# Sheet1.net
KiCad netlist of a schematic drawn in Altium Designer
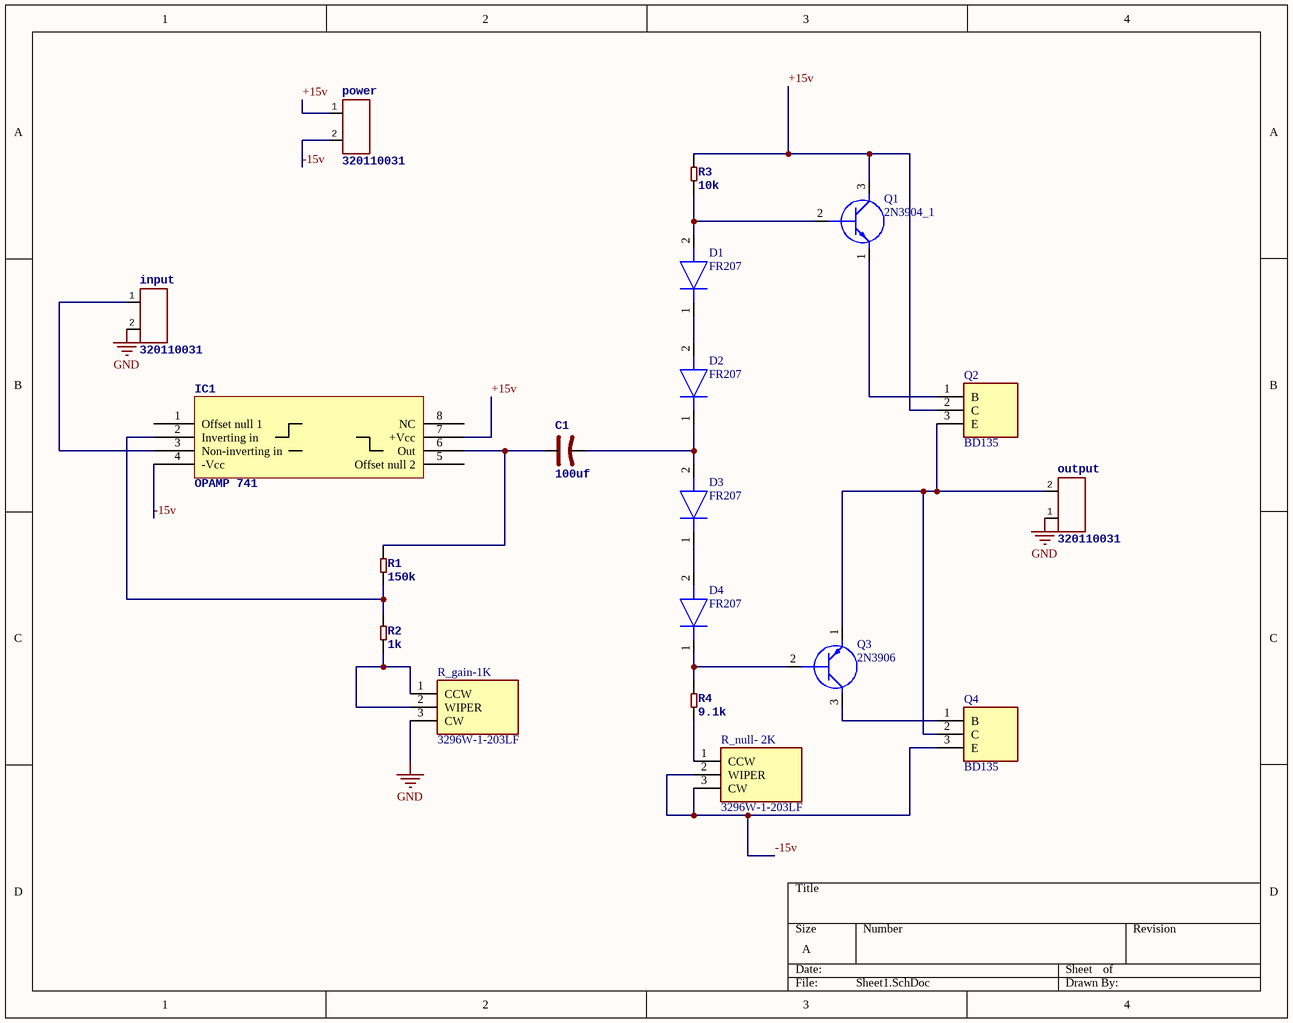
[diagram p0: Sheet1.SchDoc]

(export (version "E")
  (design (tool "Eeschema 10.0.6"))
  (components
    (comp (ref "C1")
      (value "100uf")
      (footprint "CAP TH")
      (libsource (lib "AltiumLibraryDDT") (part "CAP THT"))
    )
    (comp (ref "D1")
      (value "FR207")
      (footprint "SamacSys:DIOAD1910W90L670D310")
      (description "Diode")
      (libsource (lib "*") (part "FR207"))
    )
    (comp (ref "D2")
      (value "FR207")
      (footprint "SamacSys:DIOAD1910W90L670D310")
      (description "Diode")
      (libsource (lib "*") (part "FR207"))
    )
    (comp (ref "D3")
      (value "FR207")
      (footprint "SamacSys:DIOAD1910W90L670D310")
      (description "Diode")
      (libsource (lib "*") (part "FR207"))
    )
    (comp (ref "D4")
      (value "FR207")
      (footprint "SamacSys:DIOAD1910W90L670D310")
      (description "Diode")
      (libsource (lib "*") (part "FR207"))
    )
    (comp (ref "IC1")
      (value "OPAMP 741")
      (footprint "DIL08-ROUND")
      (libsource (lib "AltiumLibraryDDT") (part "OPAMP 741"))
    )
    (comp (ref "input")
      (value "320110031")
      (footprint "H2-5.0-10.5X8.0MM")
      (libsource (lib "AltiumLibraryDDT") (part "SCREW-TERMINAL-GREEN(2P-5.0)"))
    )
    (comp (ref "output")
      (value "320110031")
      (footprint "H2-5.0-10.5X8.0MM")
      (libsource (lib "AltiumLibraryDDT") (part "SCREW-TERMINAL-GREEN(2P-5.0)"))
    )
    (comp (ref "power")
      (value "320110031")
      (footprint "H2-5.0-10.5X8.0MM")
      (libsource (lib "AltiumLibraryDDT") (part "SCREW-TERMINAL-GREEN(2P-5.0)"))
    )
    (comp (ref "Q1")
      (value "2N3904_1")
      (footprint "SamacSys:LM431ACZ")
      (description "Transistor BJT NPN")
      (fields
        (field (name "MANUFACTURER_PART_NUMBER") "2N3904BU")
        (field (name "MOUSER PART NUMBER") "512-2N3904BU")
      )
      (libsource (lib "SamacSys") (part "2N3904_1"))
    )
    (comp (ref "Q2")
      (value "BD135")
      (footprint "SamacSys:TO254P290X760X1320-3P")
      (description "Integrated Circuit")
      (fields (field (name "MOUSER PART NUMBER") "511-BD135"))
      (libsource (lib "SamacSys") (part "BD135"))
    )
    (comp (ref "Q3")
      (value "2N3906")
      (footprint "SamacSys:2N5457")
      (description "Transistor BJT PNP")
      (fields (field (name "MOUSER PART NUMBER") "610-2N3906"))
      (libsource (lib "*") (part "2N3906"))
    )
    (comp (ref "Q4")
      (value "BD135")
      (footprint "SamacSys:TO254P290X760X1320-3P")
      (description "Integrated Circuit")
      (fields (field (name "MOUSER PART NUMBER") "511-BD135"))
      (libsource (lib "SamacSys") (part "BD135"))
    )
    (comp (ref "R1")
      (value "150k")
      (footprint "Res 1/4w")
      (libsource (lib "AltiumLibraryDDT") (part "RES_THT"))
    )
    (comp (ref "R2")
      (value "1k")
      (footprint "Res 1/4w")
      (libsource (lib "AltiumLibraryDDT") (part "RES_THT"))
    )
    (comp (ref "R3")
      (value "10k")
      (footprint "Res 1/4w")
      (libsource (lib "AltiumLibraryDDT") (part "RES_THT"))
    )
    (comp (ref "R4")
      (value "9.1k")
      (footprint "Res 1/4w")
      (libsource (lib "AltiumLibraryDDT") (part "RES_THT"))
    )
    (comp (ref "R_gain-1K")
      (value "3296W-1-203LF")
      (footprint "SamacSys:3296W-1")
      (description "Resistor")
      (fields (field (name "MOUSER PART NUMBER") "652-3296W-1-203LF"))
      (libsource (lib "*") (part "3296W-1-203LF"))
    )
    (comp (ref "R_null- 2K")
      (value "3296W-1-203LF")
      (footprint "SamacSys:3296W-1")
      (description "Resistor")
      (fields (field (name "MOUSER PART NUMBER") "652-3296W-1-203LF"))
      (libsource (lib "*") (part "3296W-1-203LF"))
    )
  )
  (nets
    (net (code "1") (name "/+15v") (class "Default")
      (node (ref "IC1") (pin "7") (pinfunction "+Vcc_7") (pintype "power_in"))
      (node (ref "Q1") (pin "3") (pinfunction "C_3") (pintype "passive"))
      (node (ref "Q2") (pin "2") (pinfunction "C_2") (pintype "passive"))
      (node (ref "R3") (pin "2") (pinfunction "2_2") (pintype "passive"))
      (node (ref "power") (pin "1") (pinfunction "1_1") (pintype "passive"))
    )
    (net (code "2") (name "/-15v") (class "Default")
      (node (ref "IC1") (pin "4") (pinfunction "-Vcc_4") (pintype "power_in"))
      (node (ref "Q4") (pin "3") (pinfunction "E_3") (pintype "passive"))
      (node (ref "R_null- 2K") (pin "2") (pinfunction "WIPER_2") (pintype "passive"))
      (node (ref "R_null- 2K") (pin "3") (pinfunction "CW_3") (pintype "passive"))
      (node (ref "power") (pin "2") (pinfunction "2_2") (pintype "passive"))
    )
    (net (code "3") (name "GND") (class "Default")
      (node (ref "R_gain-1K") (pin "3") (pinfunction "CW_3") (pintype "passive"))
      (node (ref "input") (pin "2") (pinfunction "2_2") (pintype "passive"))
      (node (ref "output") (pin "1") (pinfunction "1_1") (pintype "passive"))
    )
    (net (code "4") (name "Net-(C1-+)") (class "Default")
      (node (ref "C1") (pin "1") (pinfunction "+_1") (pintype "passive"))
      (node (ref "IC1") (pin "6") (pinfunction "Out_6") (pintype "passive"))
      (node (ref "R1") (pin "2") (pinfunction "2_2") (pintype "passive"))
    )
    (net (code "5") (name "Net-(C1--)") (class "Default")
      (node (ref "C1") (pin "2") (pinfunction "-_2") (pintype "passive"))
      (node (ref "D2") (pin "1") (pinfunction "K_1") (pintype "passive"))
      (node (ref "D3") (pin "2") (pinfunction "A_2") (pintype "passive"))
    )
    (net (code "6") (name "Net-(D1-A)") (class "Default")
      (node (ref "D1") (pin "2") (pinfunction "A_2") (pintype "passive"))
      (node (ref "Q1") (pin "2") (pinfunction "B_2") (pintype "passive"))
      (node (ref "R3") (pin "1") (pinfunction "1_1") (pintype "passive"))
    )
    (net (code "7") (name "Net-(D1-K)") (class "Default")
      (node (ref "D1") (pin "1") (pinfunction "K_1") (pintype "passive"))
      (node (ref "D2") (pin "2") (pinfunction "A_2") (pintype "passive"))
    )
    (net (code "8") (name "Net-(D3-K)") (class "Default")
      (node (ref "D3") (pin "1") (pinfunction "K_1") (pintype "passive"))
      (node (ref "D4") (pin "2") (pinfunction "A_2") (pintype "passive"))
    )
    (net (code "9") (name "Net-(D4-K)") (class "Default")
      (node (ref "D4") (pin "1") (pinfunction "K_1") (pintype "passive"))
      (node (ref "Q3") (pin "2") (pinfunction "B_2") (pintype "passive"))
      (node (ref "R4") (pin "2") (pinfunction "2_2") (pintype "passive"))
    )
    (net (code "10") (name "Net-(IC1-Inverting_in)") (class "Default")
      (node (ref "IC1") (pin "2") (pinfunction "Inverting_in_2") (pintype "passive"))
      (node (ref "R1") (pin "1") (pinfunction "1_1") (pintype "passive"))
      (node (ref "R2") (pin "2") (pinfunction "2_2") (pintype "passive"))
    )
    (net (code "11") (name "Net-(IC1-Non-inverting_in)") (class "Default")
      (node (ref "IC1") (pin "3") (pinfunction "Non-inverting_in_3") (pintype "passive"))
      (node (ref "input") (pin "1") (pinfunction "1_1") (pintype "passive"))
    )
    (net (code "12") (name "Net-(Q1-E)") (class "Default")
      (node (ref "Q1") (pin "1") (pinfunction "E_1") (pintype "passive"))
      (node (ref "Q2") (pin "1") (pinfunction "B_1") (pintype "passive"))
    )
    (net (code "13") (name "Net-(Q2-E)") (class "Default")
      (node (ref "Q2") (pin "3") (pinfunction "E_3") (pintype "passive"))
      (node (ref "Q3") (pin "1") (pinfunction "E_1") (pintype "passive"))
      (node (ref "Q4") (pin "2") (pinfunction "C_2") (pintype "passive"))
      (node (ref "output") (pin "2") (pinfunction "2_2") (pintype "passive"))
    )
    (net (code "14") (name "Net-(Q3-C)") (class "Default")
      (node (ref "Q3") (pin "3") (pinfunction "C_3") (pintype "passive"))
      (node (ref "Q4") (pin "1") (pinfunction "B_1") (pintype "passive"))
    )
    (net (code "15") (name "Net-(R_gain-1K-CCW)") (class "Default")
      (node (ref "R2") (pin "1") (pinfunction "1_1") (pintype "passive"))
      (node (ref "R_gain-1K") (pin "1") (pinfunction "CCW_1") (pintype "passive"))
      (node (ref "R_gain-1K") (pin "2") (pinfunction "WIPER_2") (pintype "passive"))
    )
    (net (code "16") (name "Net-(R_null- 2K-CCW)") (class "Default")
      (node (ref "R4") (pin "1") (pinfunction "1_1") (pintype "passive"))
      (node (ref "R_null- 2K") (pin "1") (pinfunction "CCW_1") (pintype "passive"))
    )
    (net (code "17") (name "unconnected-(IC1-NC-Pad8)") (class "Default")
      (node (ref "IC1") (pin "8") (pinfunction "NC_8") (pintype "passive"))
    )
    (net (code "18") (name "unconnected-(IC1-Offset_null_1-Pad1)") (class "Default")
      (node (ref "IC1") (pin "1") (pinfunction "Offset_null_1_1") (pintype "passive"))
    )
    (net (code "19") (name "unconnected-(IC1-Offset_null_2-Pad5)") (class "Default")
      (node (ref "IC1") (pin "5") (pinfunction "Offset_null_2_5") (pintype "passive"))
    )
  )
)
